# midiext-001.net
KiCad netlist of a schematic drawn in EAGLE
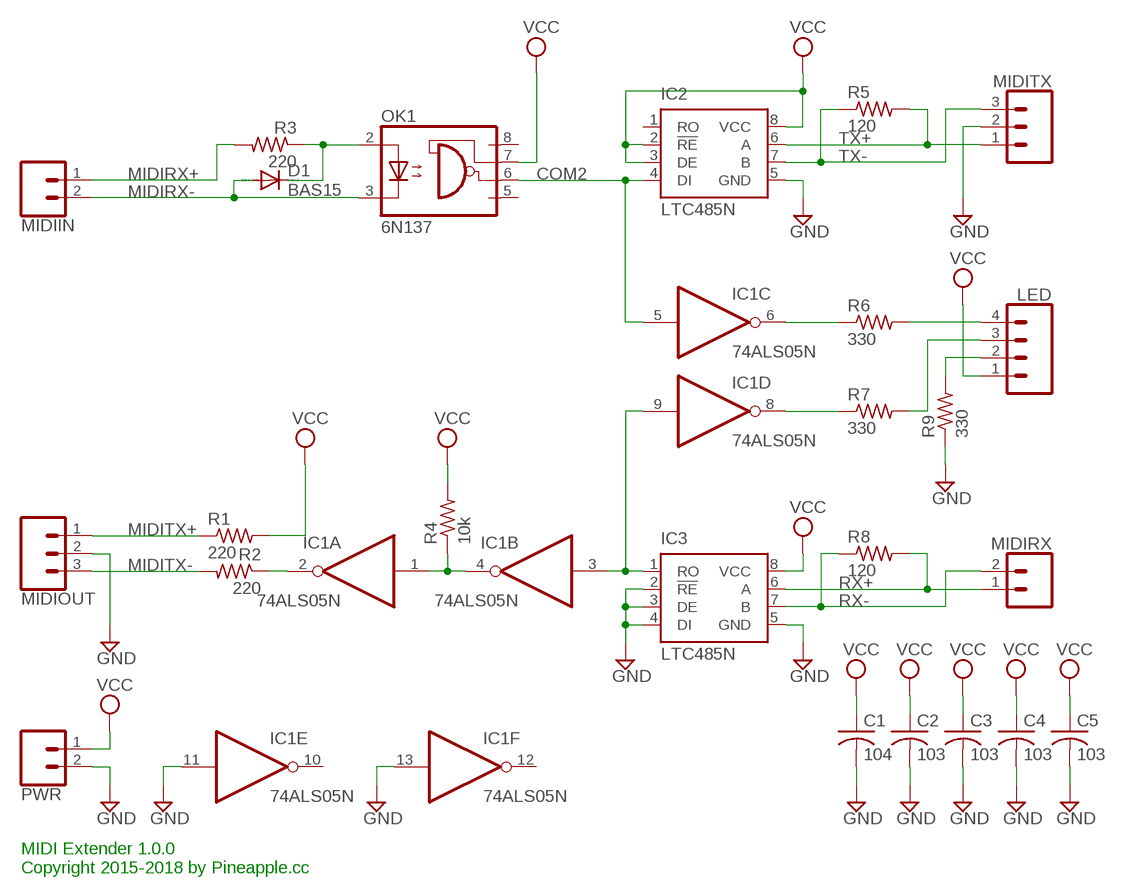
[diagram p0: schematic, sheet 1]

(export (version "E")
  (design (tool "Eeschema 10.0.6"))
  (components
    (comp (ref "C1")
      (value "104")
      (footprint "eagle-import:C025-025X050")
      (libsource (lib "eagle-import") (part "C-US025-025X050"))
    )
    (comp (ref "C2")
      (value "103")
      (footprint "eagle-import:C025-025X050")
      (libsource (lib "eagle-import") (part "C-US025-025X050"))
    )
    (comp (ref "C3")
      (value "103")
      (footprint "eagle-import:C025-025X050")
      (libsource (lib "eagle-import") (part "C-US025-025X050"))
    )
    (comp (ref "C4")
      (value "103")
      (footprint "eagle-import:C025-025X050")
      (libsource (lib "eagle-import") (part "C-US025-025X050"))
    )
    (comp (ref "C5")
      (value "103")
      (footprint "eagle-import:C025-025X050")
      (libsource (lib "eagle-import") (part "C-US025-025X050"))
    )
    (comp (ref "D1")
      (value "BAS15")
      (footprint "eagle-import:DO34-7")
      (libsource (lib "eagle-import") (part "BAS15"))
    )
    (comp (ref "IC1")
      (value "74ALS05N")
      (footprint "eagle-import:DIL14")
      (libsource (lib "eagle-import") (part "7405NALS"))
    )
    (comp (ref "IC2")
      (value "LTC485N")
      (footprint "eagle-import:DIL08")
      (libsource (lib "eagle-import") (part "LTC485N"))
    )
    (comp (ref "IC3")
      (value "LTC485N")
      (footprint "eagle-import:DIL08")
      (libsource (lib "eagle-import") (part "LTC485N"))
    )
    (comp (ref "LED")
      (value "CONN_04JST-PTH")
      (footprint "eagle-import:JST-4-PTH")
      (libsource (lib "eagle-import") (part "CONN_04JST-PTH"))
    )
    (comp (ref "MIDIIN")
      (value "CONN_02JST-PTH-2")
      (footprint "eagle-import:JST-2-PTH")
      (libsource (lib "eagle-import") (part "CONN_02JST-PTH-2"))
    )
    (comp (ref "MIDIOUT")
      (value "CONN_03JST-PTH")
      (footprint "eagle-import:JST-3-PTH")
      (libsource (lib "eagle-import") (part "CONN_03JST-PTH"))
    )
    (comp (ref "MIDIRX")
      (value "CONN_02JST-PTH-2")
      (footprint "eagle-import:JST-2-PTH")
      (libsource (lib "eagle-import") (part "CONN_02JST-PTH-2"))
    )
    (comp (ref "MIDITX")
      (value "CONN_03JST-PTH")
      (footprint "eagle-import:JST-3-PTH")
      (libsource (lib "eagle-import") (part "CONN_03JST-PTH"))
    )
    (comp (ref "OK1")
      (value "6N137")
      (footprint "eagle-import:DIL08")
      (libsource (lib "eagle-import") (part "6N137"))
    )
    (comp (ref "PWR")
      (value "CONN_02JST-PTH-2")
      (footprint "eagle-import:JST-2-PTH")
      (libsource (lib "eagle-import") (part "CONN_02JST-PTH-2"))
    )
    (comp (ref "R1")
      (value "220")
      (footprint "eagle-import:0204_5")
      (libsource (lib "eagle-import") (part "R-US_0204/5"))
    )
    (comp (ref "R2")
      (value "220")
      (footprint "eagle-import:0204_5")
      (libsource (lib "eagle-import") (part "R-US_0204/5"))
    )
    (comp (ref "R3")
      (value "220")
      (footprint "eagle-import:0204_5")
      (libsource (lib "eagle-import") (part "R-US_0204/5"))
    )
    (comp (ref "R4")
      (value "10k")
      (footprint "eagle-import:0204_5")
      (libsource (lib "eagle-import") (part "R-US_0204/5"))
    )
    (comp (ref "R5")
      (value "120")
      (footprint "eagle-import:0204_5")
      (libsource (lib "eagle-import") (part "R-US_0204/5"))
    )
    (comp (ref "R6")
      (value "330")
      (footprint "eagle-import:0204_5")
      (libsource (lib "eagle-import") (part "R-US_0204/5"))
    )
    (comp (ref "R7")
      (value "330")
      (footprint "eagle-import:0204_5")
      (libsource (lib "eagle-import") (part "R-US_0204/5"))
    )
    (comp (ref "R8")
      (value "120")
      (footprint "eagle-import:0204_5")
      (libsource (lib "eagle-import") (part "R-US_0204/5"))
    )
    (comp (ref "R9")
      (value "330")
      (footprint "eagle-import:0204_5")
      (libsource (lib "eagle-import") (part "R-US_0204/5"))
    )
  )
  (nets
    (net (code "1") (name "/COM2") (class "Default")
      (node (ref "IC1") (pin "5") (pinfunction "I_5") (pintype "input"))
      (node (ref "IC2") (pin "4") (pinfunction "DI_4") (pintype "input"))
      (node (ref "OK1") (pin "6") (pinfunction "VO_6") (pintype "passive"))
    )
    (net (code "2") (name "/MIDIRX+") (class "Default")
      (node (ref "MIDIIN") (pin "1") (pinfunction "1_1") (pintype "passive"))
      (node (ref "R3") (pin "2") (pinfunction "2_2") (pintype "passive"))
    )
    (net (code "3") (name "/MIDIRX-") (class "Default")
      (node (ref "D1") (pin "A") (pinfunction "A_A") (pintype "passive"))
      (node (ref "MIDIIN") (pin "2") (pinfunction "2_2") (pintype "passive"))
      (node (ref "OK1") (pin "3") (pinfunction "C_3") (pintype "passive"))
    )
    (net (code "4") (name "/MIDITX+") (class "Default")
      (node (ref "MIDIOUT") (pin "1") (pinfunction "1_1") (pintype "passive"))
      (node (ref "R1") (pin "1") (pinfunction "1_1") (pintype "passive"))
    )
    (net (code "5") (name "/MIDITX-") (class "Default")
      (node (ref "MIDIOUT") (pin "3") (pinfunction "3_3") (pintype "passive"))
      (node (ref "R2") (pin "2") (pinfunction "2_2") (pintype "passive"))
    )
    (net (code "6") (name "/RX+") (class "Default")
      (node (ref "IC3") (pin "6") (pinfunction "A_6") (pintype "bidirectional"))
      (node (ref "MIDIRX") (pin "1") (pinfunction "1_1") (pintype "passive"))
      (node (ref "R8") (pin "2") (pinfunction "2_2") (pintype "passive"))
    )
    (net (code "7") (name "/RX-") (class "Default")
      (node (ref "IC3") (pin "7") (pinfunction "B_7") (pintype "bidirectional"))
      (node (ref "MIDIRX") (pin "2") (pinfunction "2_2") (pintype "passive"))
      (node (ref "R8") (pin "1") (pinfunction "1_1") (pintype "passive"))
    )
    (net (code "8") (name "/TX+") (class "Default")
      (node (ref "IC2") (pin "6") (pinfunction "A_6") (pintype "bidirectional"))
      (node (ref "MIDITX") (pin "1") (pinfunction "1_1") (pintype "passive"))
      (node (ref "R5") (pin "2") (pinfunction "2_2") (pintype "passive"))
    )
    (net (code "9") (name "/TX-") (class "Default")
      (node (ref "IC2") (pin "7") (pinfunction "B_7") (pintype "bidirectional"))
      (node (ref "MIDITX") (pin "3") (pinfunction "3_3") (pintype "passive"))
      (node (ref "R5") (pin "1") (pinfunction "1_1") (pintype "passive"))
    )
    (net (code "10") (name "GND") (class "Default")
      (node (ref "C1") (pin "2") (pinfunction "2_2") (pintype "passive"))
      (node (ref "C2") (pin "2") (pinfunction "2_2") (pintype "passive"))
      (node (ref "C3") (pin "2") (pinfunction "2_2") (pintype "passive"))
      (node (ref "C4") (pin "2") (pinfunction "2_2") (pintype "passive"))
      (node (ref "C5") (pin "2") (pinfunction "2_2") (pintype "passive"))
      (node (ref "IC1") (pin "11") (pinfunction "I_11") (pintype "input"))
      (node (ref "IC1") (pin "13") (pinfunction "I_13") (pintype "input"))
      (node (ref "IC2") (pin "5") (pinfunction "GND_5") (pintype "input"))
      (node (ref "IC3") (pin "2") (pinfunction "~{RE}_2") (pintype "input"))
      (node (ref "IC3") (pin "3") (pinfunction "DE_3") (pintype "input"))
      (node (ref "IC3") (pin "4") (pinfunction "DI_4") (pintype "input"))
      (node (ref "IC3") (pin "5") (pinfunction "GND_5") (pintype "input"))
      (node (ref "MIDIOUT") (pin "2") (pinfunction "2_2") (pintype "passive"))
      (node (ref "MIDITX") (pin "2") (pinfunction "2_2") (pintype "passive"))
      (node (ref "PWR") (pin "2") (pinfunction "2_2") (pintype "passive"))
      (node (ref "R9") (pin "1") (pinfunction "1_1") (pintype "passive"))
    )
    (net (code "11") (name "Net-(IC1A-I)") (class "Default")
      (node (ref "IC1") (pin "1") (pinfunction "I_1") (pintype "input"))
      (node (ref "IC1") (pin "4") (pinfunction "O_4") (pintype "open_collector"))
      (node (ref "R4") (pin "1") (pinfunction "1_1") (pintype "passive"))
    )
    (net (code "12") (name "Net-(IC1A-O)") (class "Default")
      (node (ref "IC1") (pin "2") (pinfunction "O_2") (pintype "open_collector"))
      (node (ref "R2") (pin "1") (pinfunction "1_1") (pintype "passive"))
    )
    (net (code "13") (name "Net-(IC1B-I)") (class "Default")
      (node (ref "IC1") (pin "3") (pinfunction "I_3") (pintype "input"))
      (node (ref "IC1") (pin "9") (pinfunction "I_9") (pintype "input"))
      (node (ref "IC3") (pin "1") (pinfunction "RO_1") (pintype "output"))
    )
    (net (code "14") (name "Net-(IC1C-O)") (class "Default")
      (node (ref "IC1") (pin "6") (pinfunction "O_6") (pintype "open_collector"))
      (node (ref "R6") (pin "1") (pinfunction "1_1") (pintype "passive"))
    )
    (net (code "15") (name "Net-(IC1D-O)") (class "Default")
      (node (ref "IC1") (pin "8") (pinfunction "O_8") (pintype "open_collector"))
      (node (ref "R7") (pin "1") (pinfunction "1_1") (pintype "passive"))
    )
    (net (code "16") (name "Net-(LED-Pad2)") (class "Default")
      (node (ref "LED") (pin "2") (pinfunction "2_2") (pintype "passive"))
      (node (ref "R9") (pin "2") (pinfunction "2_2") (pintype "passive"))
    )
    (net (code "17") (name "Net-(LED-Pad3)") (class "Default")
      (node (ref "LED") (pin "3") (pinfunction "3_3") (pintype "passive"))
      (node (ref "R7") (pin "2") (pinfunction "2_2") (pintype "passive"))
    )
    (net (code "18") (name "Net-(LED-Pad4)") (class "Default")
      (node (ref "LED") (pin "4") (pinfunction "4_4") (pintype "passive"))
      (node (ref "R6") (pin "2") (pinfunction "2_2") (pintype "passive"))
    )
    (net (code "19") (name "Net-(OK1-A)") (class "Default")
      (node (ref "D1") (pin "C") (pinfunction "C_C") (pintype "passive"))
      (node (ref "OK1") (pin "2") (pinfunction "A_2") (pintype "passive"))
      (node (ref "R3") (pin "1") (pinfunction "1_1") (pintype "passive"))
    )
    (net (code "20") (name "VCC") (class "Default")
      (node (ref "C1") (pin "1") (pinfunction "1_1") (pintype "passive"))
      (node (ref "C2") (pin "1") (pinfunction "1_1") (pintype "passive"))
      (node (ref "C3") (pin "1") (pinfunction "1_1") (pintype "passive"))
      (node (ref "C4") (pin "1") (pinfunction "1_1") (pintype "passive"))
      (node (ref "C5") (pin "1") (pinfunction "1_1") (pintype "passive"))
      (node (ref "IC2") (pin "2") (pinfunction "~{RE}_2") (pintype "input"))
      (node (ref "IC2") (pin "3") (pinfunction "DE_3") (pintype "input"))
      (node (ref "IC2") (pin "8") (pinfunction "VCC_8") (pintype "input"))
      (node (ref "IC3") (pin "8") (pinfunction "VCC_8") (pintype "input"))
      (node (ref "LED") (pin "1") (pinfunction "1_1") (pintype "passive"))
      (node (ref "OK1") (pin "7") (pinfunction "VE_7") (pintype "passive"))
      (node (ref "PWR") (pin "1") (pinfunction "1_1") (pintype "passive"))
      (node (ref "R1") (pin "2") (pinfunction "2_2") (pintype "passive"))
      (node (ref "R4") (pin "2") (pinfunction "2_2") (pintype "passive"))
    )
    (net (code "21") (name "unconnected-(IC1E-O-Pad10)") (class "Default")
      (node (ref "IC1") (pin "10") (pinfunction "O_10") (pintype "open_collector"))
    )
    (net (code "22") (name "unconnected-(IC1F-O-Pad12)") (class "Default")
      (node (ref "IC1") (pin "12") (pinfunction "O_12") (pintype "open_collector"))
    )
    (net (code "23") (name "unconnected-(IC2-RO-Pad1)") (class "Default")
      (node (ref "IC2") (pin "1") (pinfunction "RO_1") (pintype "output"))
    )
    (net (code "24") (name "unconnected-(OK1-GND-Pad5)") (class "Default")
      (node (ref "OK1") (pin "5") (pinfunction "GND_5") (pintype "passive"))
    )
    (net (code "25") (name "unconnected-(OK1-VCC-Pad8)") (class "Default")
      (node (ref "OK1") (pin "8") (pinfunction "VCC_8") (pintype "passive"))
    )
  )
)
